# buck.net
KiCad netlist of a schematic drawn in Altium Designer
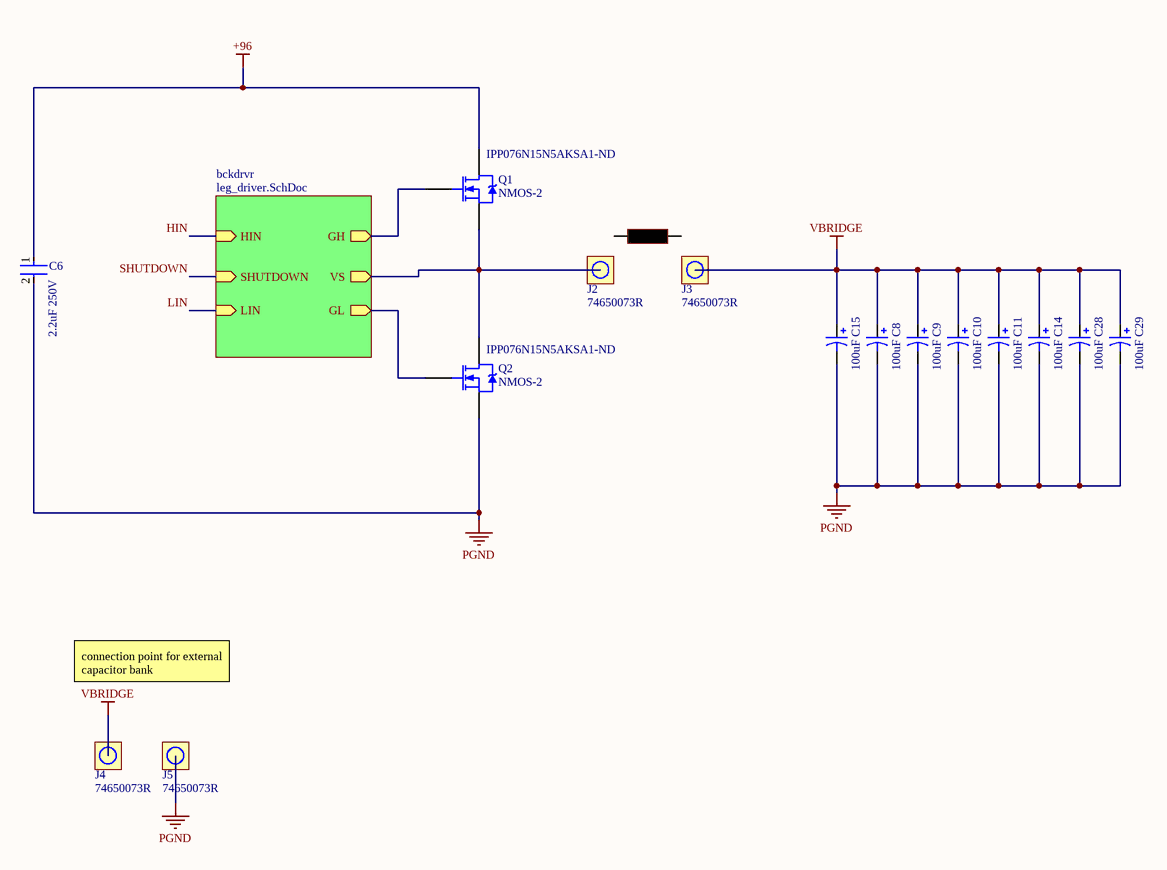
[diagram p0: buck.SchDoc]

(export (version "E")
  (design (tool "Eeschema 10.0.6"))
  (components
    (comp (ref "C6")
      (value "2.2uF 250V")
      (footprint "FP-CGA9P-IPC_B")
      (description "Cap Ceramic 2.2uF 250V X7T 20% Pad SMD 2220 +125°C Automotive T/R\r\nCGA9P3X7T2E225M250KE")
      (fields (field (name "TOLERANCE") "20%"))
      (libsource (lib "Altium Content Vault") (part "b4654b650e69147ec39a6b967a45e02"))
    )
    (comp (ref "C8")
      (value "100uF")
      (footprint "electrolyte_10mm_5mm")
      (description "Polarized Capacitor (Radial)")
      (fields (field (name "PUBLISHER") "Altium Limited"))
      (libsource (lib "Miscellaneous Devices") (part "Cap Pol1"))
    )
    (comp (ref "C9")
      (value "100uF")
      (footprint "electrolyte_10mm_5mm")
      (description "Polarized Capacitor (Radial)")
      (fields (field (name "PUBLISHER") "Altium Limited"))
      (libsource (lib "Miscellaneous Devices") (part "Cap Pol1"))
    )
    (comp (ref "C10")
      (value "100uF")
      (footprint "electrolyte_10mm_5mm")
      (description "Polarized Capacitor (Radial)")
      (fields (field (name "PUBLISHER") "Altium Limited"))
      (libsource (lib "Miscellaneous Devices") (part "Cap Pol1"))
    )
    (comp (ref "C11")
      (value "100uF")
      (footprint "electrolyte_10mm_5mm")
      (description "Polarized Capacitor (Radial)")
      (fields (field (name "PUBLISHER") "Altium Limited"))
      (libsource (lib "Miscellaneous Devices") (part "Cap Pol1"))
    )
    (comp (ref "C14")
      (value "100uF")
      (footprint "electrolyte_10mm_5mm")
      (description "Polarized Capacitor (Radial)")
      (fields (field (name "PUBLISHER") "Altium Limited"))
      (libsource (lib "Miscellaneous Devices") (part "Cap Pol1"))
    )
    (comp (ref "C15")
      (value "100uF")
      (footprint "electrolyte_10mm_5mm")
      (description "Polarized Capacitor (Radial)")
      (fields (field (name "PUBLISHER") "Altium Limited"))
      (libsource (lib "Miscellaneous Devices") (part "Cap Pol1"))
    )
    (comp (ref "C28")
      (value "100uF")
      (footprint "electrolyte_10mm_5mm")
      (description "Polarized Capacitor (Radial)")
      (fields (field (name "PUBLISHER") "Altium Limited"))
      (libsource (lib "Miscellaneous Devices") (part "Cap Pol1"))
    )
    (comp (ref "C29")
      (value "100uF")
      (footprint "electrolyte_10mm_5mm")
      (description "Polarized Capacitor (Radial)")
      (fields (field (name "PUBLISHER") "Altium Limited"))
      (libsource (lib "Miscellaneous Devices") (part "Cap Pol1"))
    )
    (comp (ref "J2")
      (value "74650073R")
      (footprint "screw_terminal")
      (description "74650073R 50A")
      (libsource (lib "coil_driver_lib") (part "screw_socket"))
    )
    (comp (ref "J3")
      (value "74650073R")
      (footprint "screw_terminal")
      (description "74650073R 50A")
      (libsource (lib "coil_driver_lib") (part "screw_socket"))
    )
    (comp (ref "J4")
      (value "74650073R")
      (footprint "screw_terminal")
      (description "74650073R 50A")
      (libsource (lib "coil_driver_lib") (part "screw_socket"))
    )
    (comp (ref "J5")
      (value "74650073R")
      (footprint "screw_terminal")
      (description "74650073R 50A")
      (libsource (lib "coil_driver_lib") (part "screw_socket"))
    )
    (comp (ref "Q1")
      (value "NMOS-2")
      (footprint "TO-220AB")
      (description "N-Channel Power MOSFET")
      (fields
        (field (name "SUPPLIER PART NUMBER 1") "IPP076N15N5AKSA1-ND")
        (field (name "PUBLISHER") "Altium Limited")
      )
      (libsource (lib "Miscellaneous Devices") (part "NMOS-2"))
    )
    (comp (ref "Q2")
      (value "NMOS-2")
      (footprint "TO-220AB")
      (description "N-Channel Power MOSFET")
      (fields
        (field (name "SUPPLIER PART NUMBER 1") "IPP076N15N5AKSA1-ND")
        (field (name "PUBLISHER") "Altium Limited")
      )
      (libsource (lib "Miscellaneous Devices") (part "NMOS-2"))
    )
  )
  (nets
    (net (code "1") (name "+96") (class "Default")
      (node (ref "C6") (pin "1") (pinfunction "1_1") (pintype "passive"))
      (node (ref "Q1") (pin "2") (pinfunction "D_2") (pintype "passive"))
    )
    (net (code "2") (name "/GH") (class "Default")
      (node (ref "Q1") (pin "1") (pinfunction "G_1") (pintype "passive"))
    )
    (net (code "3") (name "/GL") (class "Default")
      (node (ref "Q2") (pin "1") (pinfunction "G_1") (pintype "passive"))
    )
    (net (code "7") (name "/VS") (class "Default")
      (node (ref "J2") (pin "1") (pinfunction "1_1") (pintype "passive"))
      (node (ref "Q1") (pin "3") (pinfunction "S_3") (pintype "passive"))
      (node (ref "Q2") (pin "2") (pinfunction "D_2") (pintype "passive"))
    )
    (net (code "8") (name "PGND") (class "Default")
      (node (ref "C10") (pin "2") (pinfunction "2_2") (pintype "passive"))
      (node (ref "C11") (pin "2") (pinfunction "2_2") (pintype "passive"))
      (node (ref "C14") (pin "2") (pinfunction "2_2") (pintype "passive"))
      (node (ref "C15") (pin "2") (pinfunction "2_2") (pintype "passive"))
      (node (ref "C28") (pin "2") (pinfunction "2_2") (pintype "passive"))
      (node (ref "C29") (pin "2") (pinfunction "2_2") (pintype "passive"))
      (node (ref "C6") (pin "2") (pinfunction "2_2") (pintype "passive"))
      (node (ref "C8") (pin "2") (pinfunction "2_2") (pintype "passive"))
      (node (ref "C9") (pin "2") (pinfunction "2_2") (pintype "passive"))
      (node (ref "J5") (pin "1") (pinfunction "1_1") (pintype "passive"))
      (node (ref "Q2") (pin "3") (pinfunction "S_3") (pintype "passive"))
    )
    (net (code "9") (name "VBRIDGE") (class "Default")
      (node (ref "C10") (pin "1") (pinfunction "1_1") (pintype "passive"))
      (node (ref "C11") (pin "1") (pinfunction "1_1") (pintype "passive"))
      (node (ref "C14") (pin "1") (pinfunction "1_1") (pintype "passive"))
      (node (ref "C15") (pin "1") (pinfunction "1_1") (pintype "passive"))
      (node (ref "C28") (pin "1") (pinfunction "1_1") (pintype "passive"))
      (node (ref "C29") (pin "1") (pinfunction "1_1") (pintype "passive"))
      (node (ref "C8") (pin "1") (pinfunction "1_1") (pintype "passive"))
      (node (ref "C9") (pin "1") (pinfunction "1_1") (pintype "passive"))
      (node (ref "J3") (pin "1") (pinfunction "1_1") (pintype "passive"))
      (node (ref "J4") (pin "1") (pinfunction "1_1") (pintype "passive"))
    )
  )
)
